# PVScontroller_v1_1_with_logo.net
KiCad netlist of a schematic drawn in EAGLE
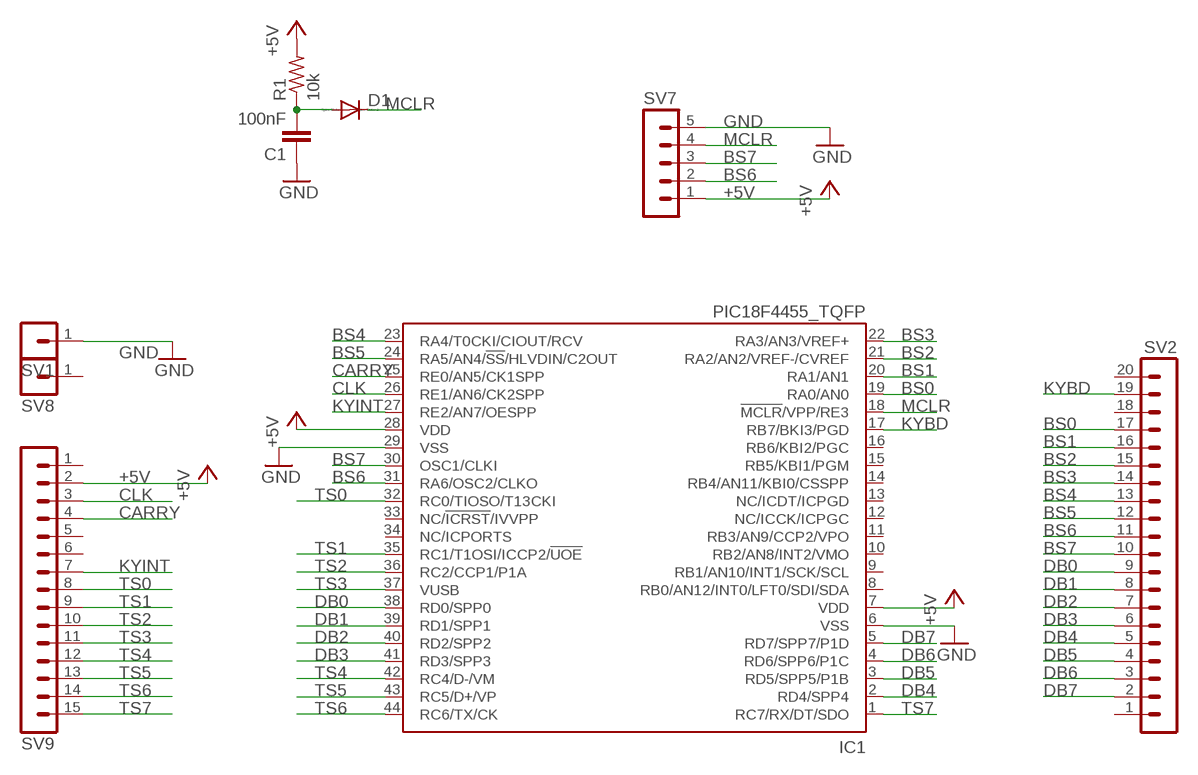
[diagram p0: schematic, sheet 1]

(export (version "E")
  (design (tool "Eeschema 10.0.6"))
  (components
    (comp (ref "C1")
      (value "100nF")
      (footprint "eagle-import:C0805")
      (libsource (lib "eagle-import") (part "C-EUC0805"))
    )
    (comp (ref "D1")
      (value "DIODE-SOD80C")
      (footprint "eagle-import:SOD80C")
      (libsource (lib "eagle-import") (part "DIODE-SOD80C"))
    )
    (comp (ref "IC1")
      (value "PIC18F4455_TQFP")
      (footprint "eagle-import:TQFP44")
      (fields (field (name "MF") "MICROCHIP") (field (name "MPN") "PIC18F4455-I/PT"))
      (libsource (lib "eagle-import") (part "PIC18F4_TQFP455"))
    )
    (comp (ref "R1")
      (value "10k")
      (footprint "eagle-import:R0805")
      (libsource (lib "eagle-import") (part "R-US_R0805"))
    )
    (comp (ref "SV1")
      (value "MA01-1")
      (footprint "eagle-import:MA01-1")
      (libsource (lib "eagle-import") (part "MA01-1"))
    )
    (comp (ref "SV2")
      (value "MA20-1")
      (footprint "eagle-import:MA20-1")
      (libsource (lib "eagle-import") (part "MA20-1"))
    )
    (comp (ref "SV7")
      (value "MA05-1")
      (footprint "eagle-import:MA05-1")
      (libsource (lib "eagle-import") (part "MA05-1"))
    )
    (comp (ref "SV8")
      (value "MA01-1")
      (footprint "eagle-import:MA01-1")
      (libsource (lib "eagle-import") (part "MA01-1"))
    )
    (comp (ref "SV9")
      (value "MA15-1")
      (footprint "eagle-import:MA15-1")
      (libsource (lib "eagle-import") (part "MA15-1"))
    )
  )
  (nets
    (net (code "1") (name "+5V") (class "Default")
      (node (ref "IC1") (pin "28") (pinfunction "VDD_28") (pintype "power_in"))
      (node (ref "IC1") (pin "7") (pinfunction "VDD_7") (pintype "power_in"))
      (node (ref "R1") (pin "2") (pinfunction "2_2") (pintype "passive"))
      (node (ref "SV7") (pin "1") (pinfunction "1_1") (pintype "passive"))
      (node (ref "SV9") (pin "2") (pinfunction "2_2") (pintype "passive"))
    )
    (net (code "2") (name "/BS0") (class "Default")
      (node (ref "IC1") (pin "19") (pinfunction "RA0/AN0_19") (pintype "bidirectional"))
      (node (ref "SV2") (pin "17") (pinfunction "17_17") (pintype "passive"))
    )
    (net (code "3") (name "/BS1") (class "Default")
      (node (ref "IC1") (pin "20") (pinfunction "RA1/AN1_20") (pintype "bidirectional"))
      (node (ref "SV2") (pin "16") (pinfunction "16_16") (pintype "passive"))
    )
    (net (code "4") (name "/BS2") (class "Default")
      (node (ref "IC1") (pin "21") (pinfunction "RA2/AN2/VREF-/CVREF_21") (pintype "bidirectional"))
      (node (ref "SV2") (pin "15") (pinfunction "15_15") (pintype "passive"))
    )
    (net (code "5") (name "/BS3") (class "Default")
      (node (ref "IC1") (pin "22") (pinfunction "RA3/AN3/VREF+_22") (pintype "bidirectional"))
      (node (ref "SV2") (pin "14") (pinfunction "14_14") (pintype "passive"))
    )
    (net (code "6") (name "/BS4") (class "Default")
      (node (ref "IC1") (pin "23") (pinfunction "RA4/T0CKI/CIOUT/RCV_23") (pintype "bidirectional"))
      (node (ref "SV2") (pin "13") (pinfunction "13_13") (pintype "passive"))
    )
    (net (code "7") (name "/BS5") (class "Default")
      (node (ref "IC1") (pin "24") (pinfunction "RA5/AN4/~{SS}/HLVDIN/C2OUT_24") (pintype "bidirectional"))
      (node (ref "SV2") (pin "12") (pinfunction "12_12") (pintype "passive"))
    )
    (net (code "8") (name "/BS6") (class "Default")
      (node (ref "IC1") (pin "31") (pinfunction "RA6/OSC2/CLKO_31") (pintype "output"))
      (node (ref "SV2") (pin "11") (pinfunction "11_11") (pintype "passive"))
      (node (ref "SV7") (pin "2") (pinfunction "2_2") (pintype "passive"))
    )
    (net (code "9") (name "/BS7") (class "Default")
      (node (ref "IC1") (pin "30") (pinfunction "OSC1/CLKI_30") (pintype "input"))
      (node (ref "SV2") (pin "10") (pinfunction "10_10") (pintype "passive"))
      (node (ref "SV7") (pin "3") (pinfunction "3_3") (pintype "passive"))
    )
    (net (code "10") (name "/CARRY") (class "Default")
      (node (ref "IC1") (pin "25") (pinfunction "RE0/AN5/CK1SPP_25") (pintype "bidirectional"))
      (node (ref "SV9") (pin "4") (pinfunction "4_4") (pintype "passive"))
    )
    (net (code "11") (name "/CLK") (class "Default")
      (node (ref "IC1") (pin "26") (pinfunction "RE1/AN6/CK2SPP_26") (pintype "bidirectional"))
      (node (ref "SV9") (pin "3") (pinfunction "3_3") (pintype "passive"))
    )
    (net (code "12") (name "/DB0") (class "Default")
      (node (ref "IC1") (pin "38") (pinfunction "RD0/SPP0_38") (pintype "bidirectional"))
      (node (ref "SV2") (pin "9") (pinfunction "9_9") (pintype "passive"))
    )
    (net (code "13") (name "/DB1") (class "Default")
      (node (ref "IC1") (pin "39") (pinfunction "RD1/SPP1_39") (pintype "bidirectional"))
      (node (ref "SV2") (pin "8") (pinfunction "8_8") (pintype "passive"))
    )
    (net (code "14") (name "/DB2") (class "Default")
      (node (ref "IC1") (pin "40") (pinfunction "RD2/SPP2_40") (pintype "bidirectional"))
      (node (ref "SV2") (pin "7") (pinfunction "7_7") (pintype "passive"))
    )
    (net (code "15") (name "/DB3") (class "Default")
      (node (ref "IC1") (pin "41") (pinfunction "RD3/SPP3_41") (pintype "bidirectional"))
      (node (ref "SV2") (pin "6") (pinfunction "6_6") (pintype "passive"))
    )
    (net (code "16") (name "/DB4") (class "Default")
      (node (ref "IC1") (pin "2") (pinfunction "RD4/SPP4_2") (pintype "bidirectional"))
      (node (ref "SV2") (pin "5") (pinfunction "5_5") (pintype "passive"))
    )
    (net (code "17") (name "/DB5") (class "Default")
      (node (ref "IC1") (pin "3") (pinfunction "RD5/SPP5/P1B_3") (pintype "bidirectional"))
      (node (ref "SV2") (pin "4") (pinfunction "4_4") (pintype "passive"))
    )
    (net (code "18") (name "/DB6") (class "Default")
      (node (ref "IC1") (pin "4") (pinfunction "RD6/SPP6/P1C_4") (pintype "bidirectional"))
      (node (ref "SV2") (pin "3") (pinfunction "3_3") (pintype "passive"))
    )
    (net (code "19") (name "/DB7") (class "Default")
      (node (ref "IC1") (pin "5") (pinfunction "RD7/SPP7/P1D_5") (pintype "bidirectional"))
      (node (ref "SV2") (pin "2") (pinfunction "2_2") (pintype "passive"))
    )
    (net (code "20") (name "/KYBD") (class "Default")
      (node (ref "IC1") (pin "17") (pinfunction "RB7/BKI3/PGD_17") (pintype "bidirectional"))
      (node (ref "SV2") (pin "19") (pinfunction "19_19") (pintype "passive"))
    )
    (net (code "21") (name "/KYINT") (class "Default")
      (node (ref "IC1") (pin "27") (pinfunction "RE2/AN7/OESPP_27") (pintype "bidirectional"))
      (node (ref "SV9") (pin "7") (pinfunction "7_7") (pintype "passive"))
    )
    (net (code "22") (name "/MCLR") (class "Default")
      (node (ref "D1") (pin "C") (pinfunction "C_C") (pintype "passive"))
      (node (ref "IC1") (pin "18") (pinfunction "~{MCLR}/VPP/RE3_18") (pintype "input"))
      (node (ref "SV7") (pin "4") (pinfunction "4_4") (pintype "passive"))
    )
    (net (code "23") (name "/TS0") (class "Default")
      (node (ref "IC1") (pin "32") (pinfunction "RC0/TIOSO/T13CKI_32") (pintype "bidirectional"))
      (node (ref "SV9") (pin "8") (pinfunction "8_8") (pintype "passive"))
    )
    (net (code "24") (name "/TS1") (class "Default")
      (node (ref "IC1") (pin "35") (pinfunction "RC1/T1OSI/ICCP2/~{UOE}_35") (pintype "bidirectional"))
      (node (ref "SV9") (pin "9") (pinfunction "9_9") (pintype "passive"))
    )
    (net (code "25") (name "/TS2") (class "Default")
      (node (ref "IC1") (pin "36") (pinfunction "RC2/CCP1/P1A_36") (pintype "bidirectional"))
      (node (ref "SV9") (pin "10") (pinfunction "10_10") (pintype "passive"))
    )
    (net (code "26") (name "/TS3") (class "Default")
      (node (ref "IC1") (pin "37") (pinfunction "VUSB_37") (pintype "bidirectional"))
      (node (ref "SV9") (pin "11") (pinfunction "11_11") (pintype "passive"))
    )
    (net (code "27") (name "/TS4") (class "Default")
      (node (ref "IC1") (pin "42") (pinfunction "RC4/D-/VM_42") (pintype "bidirectional"))
      (node (ref "SV9") (pin "12") (pinfunction "12_12") (pintype "passive"))
    )
    (net (code "28") (name "/TS5") (class "Default")
      (node (ref "IC1") (pin "43") (pinfunction "RC5/D+/VP_43") (pintype "bidirectional"))
      (node (ref "SV9") (pin "13") (pinfunction "13_13") (pintype "passive"))
    )
    (net (code "29") (name "/TS6") (class "Default")
      (node (ref "IC1") (pin "44") (pinfunction "RC6/TX/CK_44") (pintype "bidirectional"))
      (node (ref "SV9") (pin "14") (pinfunction "14_14") (pintype "passive"))
    )
    (net (code "30") (name "/TS7") (class "Default")
      (node (ref "IC1") (pin "1") (pinfunction "RC7/RX/DT/SDO_1") (pintype "bidirectional"))
      (node (ref "SV9") (pin "15") (pinfunction "15_15") (pintype "passive"))
    )
    (net (code "31") (name "GND") (class "Default")
      (node (ref "C1") (pin "1") (pinfunction "1_1") (pintype "passive"))
      (node (ref "IC1") (pin "29") (pinfunction "VSS_29") (pintype "power_in"))
      (node (ref "IC1") (pin "6") (pinfunction "VSS_6") (pintype "power_in"))
      (node (ref "SV1") (pin "1") (pinfunction "1_1") (pintype "passive"))
      (node (ref "SV7") (pin "5") (pinfunction "5_5") (pintype "passive"))
    )
    (net (code "32") (name "Net-(C1-Pad2)") (class "Default")
      (node (ref "C1") (pin "2") (pinfunction "2_2") (pintype "passive"))
      (node (ref "D1") (pin "A") (pinfunction "A_A") (pintype "passive"))
      (node (ref "R1") (pin "1") (pinfunction "1_1") (pintype "passive"))
    )
    (net (code "33") (name "unconnected-(IC1-NC{slash}ICCK{slash}ICPGC-Pad12)") (class "Default")
      (node (ref "IC1") (pin "12") (pinfunction "NC/ICCK/ICPGC_12") (pintype "bidirectional"))
    )
    (net (code "34") (name "unconnected-(IC1-NC{slash}ICDT{slash}ICPGD-Pad13)") (class "Default")
      (node (ref "IC1") (pin "13") (pinfunction "NC/ICDT/ICPGD_13") (pintype "bidirectional"))
    )
    (net (code "35") (name "unconnected-(IC1-NC{slash}ICPORTS-Pad34)") (class "Default")
      (node (ref "IC1") (pin "34") (pinfunction "NC/ICPORTS_34") (pintype "input"))
    )
    (net (code "36") (name "unconnected-(IC1-NC{slash}~{ICRST}{slash}IVVPP-Pad33)") (class "Default")
      (node (ref "IC1") (pin "33") (pinfunction "NC/~{ICRST}/IVVPP_33") (pintype "input"))
    )
    (net (code "37") (name "unconnected-(IC1-RB0{slash}AN12{slash}INT0{slash}LFT0{slash}SDI{slash}SDA-Pad8)") (class "Default")
      (node (ref "IC1") (pin "8") (pinfunction "RB0/AN12/INT0/LFT0/SDI/SDA_8") (pintype "bidirectional"))
    )
    (net (code "38") (name "unconnected-(IC1-RB1{slash}AN10{slash}INT1{slash}SCK{slash}SCL-Pad9)") (class "Default")
      (node (ref "IC1") (pin "9") (pinfunction "RB1/AN10/INT1/SCK/SCL_9") (pintype "bidirectional"))
    )
    (net (code "39") (name "unconnected-(IC1-RB2{slash}AN8{slash}INT2{slash}VMO-Pad10)") (class "Default")
      (node (ref "IC1") (pin "10") (pinfunction "RB2/AN8/INT2/VMO_10") (pintype "bidirectional"))
    )
    (net (code "40") (name "unconnected-(IC1-RB3{slash}AN9{slash}CCP2{slash}VPO-Pad11)") (class "Default")
      (node (ref "IC1") (pin "11") (pinfunction "RB3/AN9/CCP2/VPO_11") (pintype "bidirectional"))
    )
    (net (code "41") (name "unconnected-(IC1-RB4{slash}AN11{slash}KBI0{slash}CSSPP-Pad14)") (class "Default")
      (node (ref "IC1") (pin "14") (pinfunction "RB4/AN11/KBI0/CSSPP_14") (pintype "bidirectional"))
    )
    (net (code "42") (name "unconnected-(IC1-RB5{slash}KBI1{slash}PGM-Pad15)") (class "Default")
      (node (ref "IC1") (pin "15") (pinfunction "RB5/KBI1/PGM_15") (pintype "bidirectional"))
    )
    (net (code "43") (name "unconnected-(IC1-RB6{slash}KBI2{slash}PGC-Pad16)") (class "Default")
      (node (ref "IC1") (pin "16") (pinfunction "RB6/KBI2/PGC_16") (pintype "bidirectional"))
    )
    (net (code "44") (name "unconnected-(SV2-Pad1)") (class "Default")
      (node (ref "SV2") (pin "1") (pinfunction "1_1") (pintype "passive"))
    )
    (net (code "45") (name "unconnected-(SV2-Pad18)") (class "Default")
      (node (ref "SV2") (pin "18") (pinfunction "18_18") (pintype "passive"))
    )
    (net (code "46") (name "unconnected-(SV2-Pad20)") (class "Default")
      (node (ref "SV2") (pin "20") (pinfunction "20_20") (pintype "passive"))
    )
    (net (code "47") (name "unconnected-(SV8-Pad1)") (class "Default")
      (node (ref "SV8") (pin "1") (pinfunction "1_1") (pintype "passive"))
    )
    (net (code "48") (name "unconnected-(SV9-Pad1)") (class "Default")
      (node (ref "SV9") (pin "1") (pinfunction "1_1") (pintype "passive"))
    )
    (net (code "49") (name "unconnected-(SV9-Pad5)") (class "Default")
      (node (ref "SV9") (pin "5") (pinfunction "5_5") (pintype "passive"))
    )
    (net (code "50") (name "unconnected-(SV9-Pad6)") (class "Default")
      (node (ref "SV9") (pin "6") (pinfunction "6_6") (pintype "passive"))
    )
  )
)
